# Prototype_V0_2.net
KiCad netlist of a schematic drawn in EAGLE
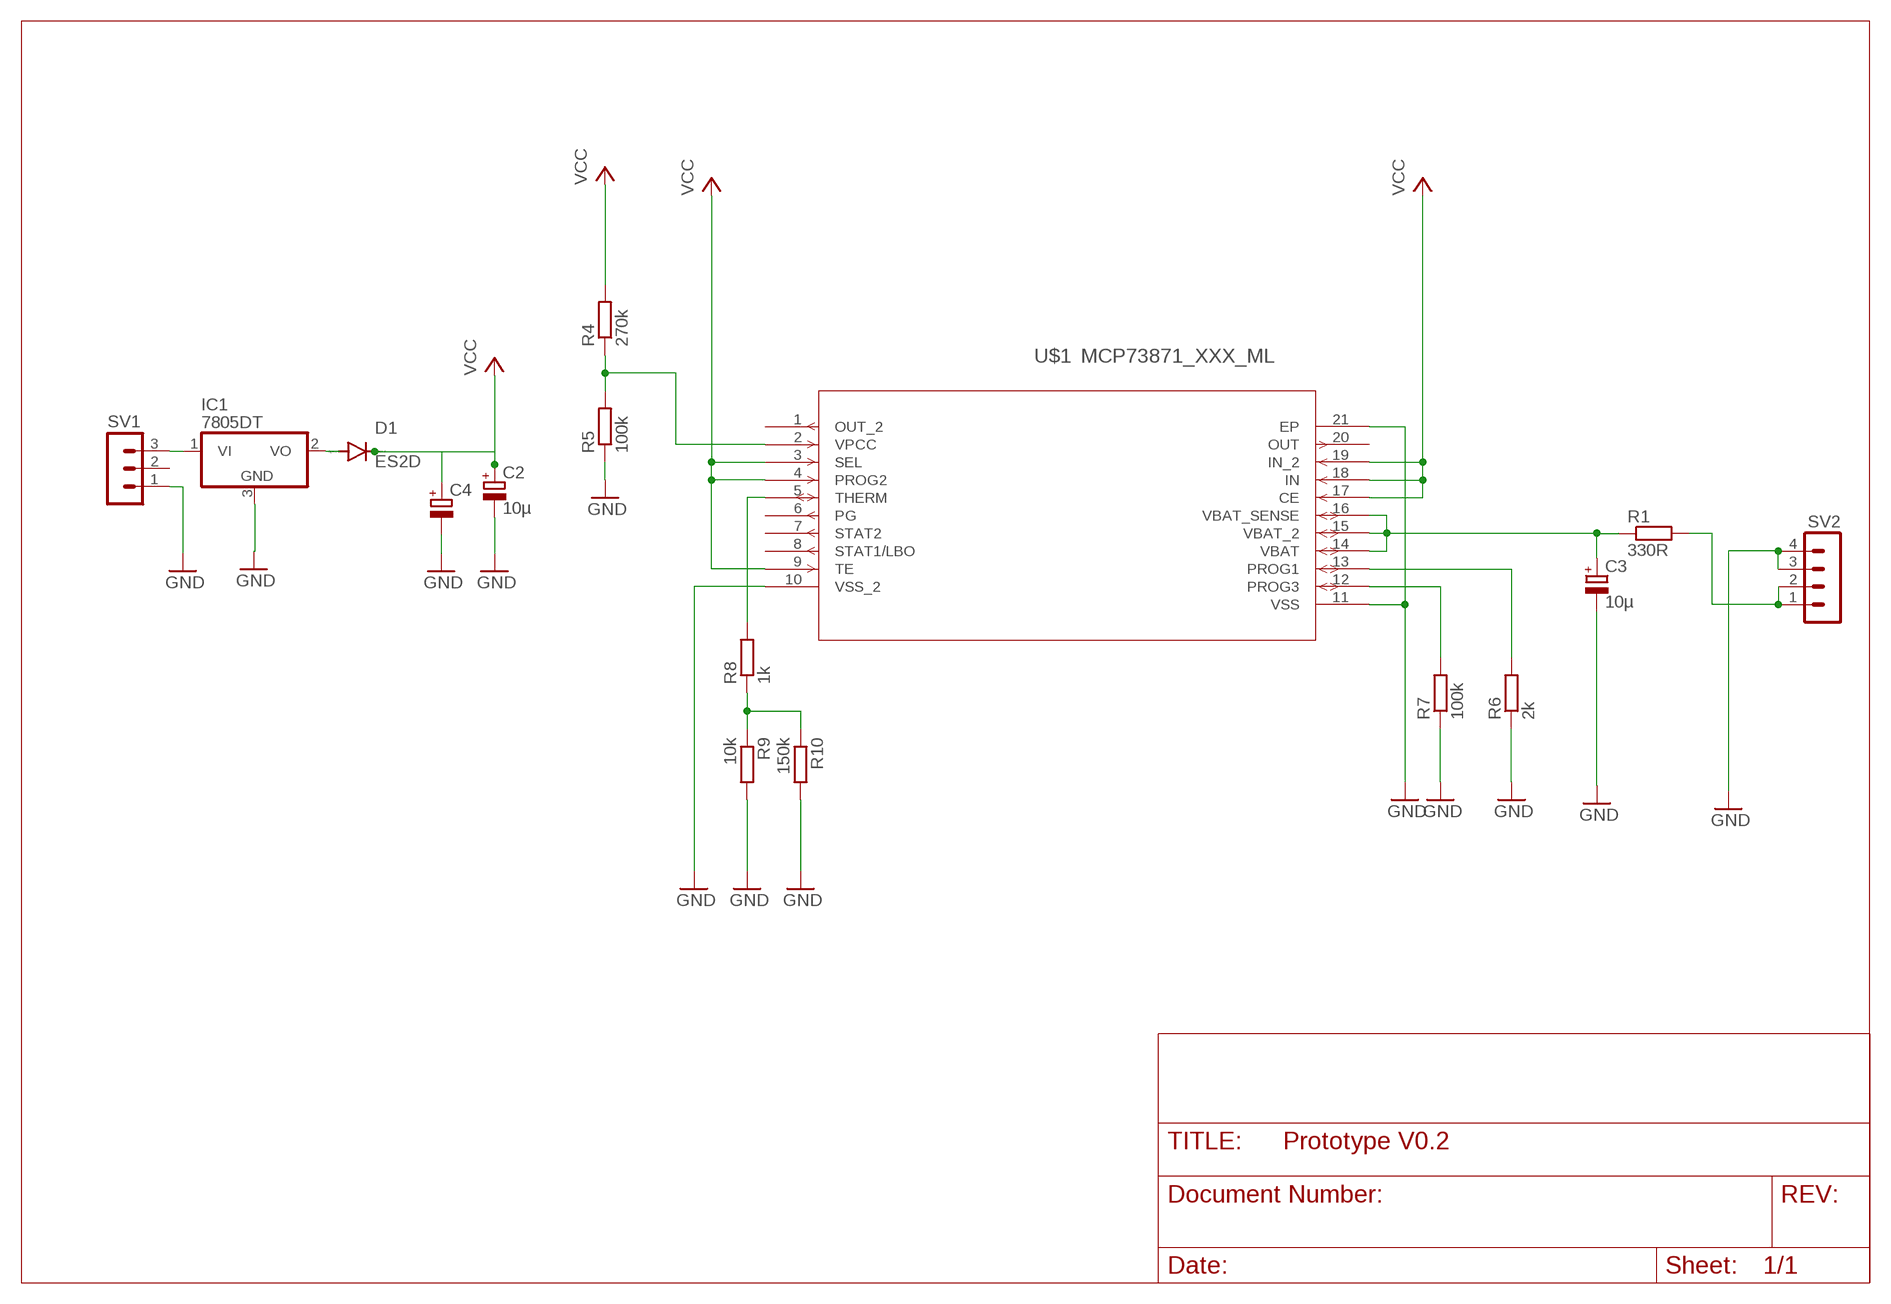
[diagram p0: schematic, sheet 1]

(export (version "E")
  (design (tool "Eeschema 10.0.6"))
  (components
    (comp (ref "C2")
      (value "10µ")
      (footprint "eagle-import:153CLV-0505")
      (libsource (lib "eagle-import") (part "CPOL-EU153CLV-0505"))
    )
    (comp (ref "C3")
      (value "10µ")
      (footprint "eagle-import:153CLV-0505")
      (libsource (lib "eagle-import") (part "CPOL-EU153CLV-0505"))
    )
    (comp (ref "C4")
      (value "CPOL-EUE2.5-6")
      (footprint "eagle-import:E2,5-6")
      (libsource (lib "eagle-import") (part "CPOL-EUE2.5-6"))
    )
    (comp (ref "D1")
      (value "ES2D")
      (footprint "eagle-import:SMB")
      (libsource (lib "eagle-import") (part "ES2D"))
    )
    (comp (ref "IC1")
      (value "7805DT")
      (footprint "eagle-import:TO252")
      (libsource (lib "eagle-import") (part "78DT05"))
    )
    (comp (ref "R1")
      (value "330R")
      (footprint "eagle-import:R0603")
      (libsource (lib "eagle-import") (part "R-EU_R0603"))
    )
    (comp (ref "R4")
      (value "270k")
      (footprint "eagle-import:R0603")
      (libsource (lib "eagle-import") (part "R-EU_R0603"))
    )
    (comp (ref "R5")
      (value "100k")
      (footprint "eagle-import:R0603")
      (libsource (lib "eagle-import") (part "R-EU_R0603"))
    )
    (comp (ref "R6")
      (value "2k")
      (footprint "eagle-import:R0603")
      (libsource (lib "eagle-import") (part "R-EU_R0603"))
    )
    (comp (ref "R7")
      (value "100k")
      (footprint "eagle-import:R0603")
      (libsource (lib "eagle-import") (part "R-EU_R0603"))
    )
    (comp (ref "R8")
      (value "1k")
      (footprint "eagle-import:R0603")
      (libsource (lib "eagle-import") (part "R-EU_R0603"))
    )
    (comp (ref "R9")
      (value "10k")
      (footprint "eagle-import:R0603")
      (libsource (lib "eagle-import") (part "R-EU_R0603"))
    )
    (comp (ref "R10")
      (value "150k")
      (footprint "eagle-import:R0603")
      (libsource (lib "eagle-import") (part "R-EU_R0603"))
    )
    (comp (ref "SV1")
      (value "MA03-1")
      (footprint "eagle-import:MA03-1")
      (libsource (lib "eagle-import") (part "MA03-1"))
    )
    (comp (ref "SV2")
      (value "MA04-1")
      (footprint "eagle-import:MA04-1")
      (libsource (lib "eagle-import") (part "MA04-1"))
    )
    (comp (ref "U$1")
      (value "MCP73871_XXX_ML")
      (footprint "eagle-import:QFN20_4X4MC")
      (libsource (lib "eagle-import") (part "MCP73871_XXX_ML"))
    )
  )
  (nets
    (net (code "1") (name "GND") (class "Default")
      (node (ref "C2") (pin "-") (pinfunction "-_-") (pintype "passive"))
      (node (ref "C3") (pin "-") (pinfunction "-_-") (pintype "passive"))
      (node (ref "C4") (pin "-") (pinfunction "-_-") (pintype "passive"))
      (node (ref "IC1") (pin "3") (pinfunction "GND_3") (pintype "passive"))
      (node (ref "R10") (pin "2") (pinfunction "2_2") (pintype "passive"))
      (node (ref "R5") (pin "1") (pinfunction "1_1") (pintype "passive"))
      (node (ref "R6") (pin "1") (pinfunction "1_1") (pintype "passive"))
      (node (ref "R7") (pin "1") (pinfunction "1_1") (pintype "passive"))
      (node (ref "R9") (pin "2") (pinfunction "2_2") (pintype "passive"))
      (node (ref "SV1") (pin "1") (pinfunction "1_1") (pintype "passive"))
      (node (ref "SV2") (pin "3") (pinfunction "3_3") (pintype "passive"))
      (node (ref "SV2") (pin "4") (pinfunction "4_4") (pintype "passive"))
      (node (ref "U$1") (pin "10") (pinfunction "VSS_2_10") (pintype "power_in"))
      (node (ref "U$1") (pin "11") (pinfunction "VSS_11") (pintype "power_in"))
      (node (ref "U$1") (pin "21") (pinfunction "EP_21") (pintype "passive"))
    )
    (net (code "2") (name "Net-(IC1-VI)") (class "Default")
      (node (ref "IC1") (pin "1") (pinfunction "VI_1") (pintype "input"))
      (node (ref "SV1") (pin "3") (pinfunction "3_3") (pintype "passive"))
    )
    (net (code "3") (name "Net-(IC1-VO)") (class "Default")
      (node (ref "D1") (pin "A") (pinfunction "A_A") (pintype "passive"))
      (node (ref "IC1") (pin "2") (pinfunction "VO_2") (pintype "passive"))
    )
    (net (code "4") (name "Net-(R1-Pad2)") (class "Default")
      (node (ref "R1") (pin "2") (pinfunction "2_2") (pintype "passive"))
      (node (ref "SV2") (pin "1") (pinfunction "1_1") (pintype "passive"))
      (node (ref "SV2") (pin "2") (pinfunction "2_2") (pintype "passive"))
    )
    (net (code "5") (name "Net-(R10-Pad1)") (class "Default")
      (node (ref "R10") (pin "1") (pinfunction "1_1") (pintype "passive"))
      (node (ref "R8") (pin "1") (pinfunction "1_1") (pintype "passive"))
      (node (ref "R9") (pin "1") (pinfunction "1_1") (pintype "passive"))
    )
    (net (code "6") (name "Net-(U$1-PROG1)") (class "Default")
      (node (ref "R6") (pin "2") (pinfunction "2_2") (pintype "passive"))
      (node (ref "U$1") (pin "13") (pinfunction "PROG1_13") (pintype "bidirectional"))
    )
    (net (code "7") (name "Net-(U$1-PROG3)") (class "Default")
      (node (ref "R7") (pin "2") (pinfunction "2_2") (pintype "passive"))
      (node (ref "U$1") (pin "12") (pinfunction "PROG3_12") (pintype "bidirectional"))
    )
    (net (code "8") (name "Net-(U$1-THERM)") (class "Default")
      (node (ref "R8") (pin "2") (pinfunction "2_2") (pintype "passive"))
      (node (ref "U$1") (pin "5") (pinfunction "THERM_5") (pintype "bidirectional"))
    )
    (net (code "9") (name "Net-(U$1-VBAT)") (class "Default")
      (node (ref "C3") (pin "+") (pinfunction "+_+") (pintype "passive"))
      (node (ref "U$1") (pin "14") (pinfunction "VBAT_14") (pintype "bidirectional"))
      (node (ref "U$1") (pin "15") (pinfunction "VBAT_2_15") (pintype "bidirectional"))
      (node (ref "U$1") (pin "16") (pinfunction "VBAT_SENSE_16") (pintype "bidirectional"))
    )
    (net (code "10") (name "Net-(U$1-VPCC)") (class "Default")
      (node (ref "R4") (pin "1") (pinfunction "1_1") (pintype "passive"))
      (node (ref "R5") (pin "2") (pinfunction "2_2") (pintype "passive"))
      (node (ref "U$1") (pin "2") (pinfunction "VPCC_2") (pintype "input"))
    )
    (net (code "11") (name "VCC") (class "Default")
      (node (ref "C2") (pin "+") (pinfunction "+_+") (pintype "passive"))
      (node (ref "C4") (pin "+") (pinfunction "+_+") (pintype "passive"))
      (node (ref "D1") (pin "C") (pinfunction "C_C") (pintype "passive"))
      (node (ref "R4") (pin "2") (pinfunction "2_2") (pintype "passive"))
      (node (ref "U$1") (pin "17") (pinfunction "CE_17") (pintype "input"))
      (node (ref "U$1") (pin "18") (pinfunction "IN_18") (pintype "input"))
      (node (ref "U$1") (pin "19") (pinfunction "IN_2_19") (pintype "input"))
      (node (ref "U$1") (pin "3") (pinfunction "SEL_3") (pintype "input"))
      (node (ref "U$1") (pin "4") (pinfunction "PROG2_4") (pintype "input"))
      (node (ref "U$1") (pin "9") (pinfunction "TE_9") (pintype "input"))
    )
    (net (code "12") (name "unconnected-(R1-Pad1)") (class "Default")
      (node (ref "R1") (pin "1") (pinfunction "1_1") (pintype "passive"))
    )
    (net (code "13") (name "unconnected-(SV1-Pad2)") (class "Default")
      (node (ref "SV1") (pin "2") (pinfunction "2_2") (pintype "passive"))
    )
    (net (code "14") (name "unconnected-(U$1-OUT-Pad20)") (class "Default")
      (node (ref "U$1") (pin "20") (pinfunction "OUT_20") (pintype "output"))
    )
    (net (code "15") (name "unconnected-(U$1-OUT_2-Pad1)") (class "Default")
      (node (ref "U$1") (pin "1") (pinfunction "OUT_2_1") (pintype "output"))
    )
    (net (code "16") (name "unconnected-(U$1-PG-Pad6)") (class "Default")
      (node (ref "U$1") (pin "6") (pinfunction "PG_6") (pintype "output"))
    )
    (net (code "17") (name "unconnected-(U$1-STAT1{slash}LBO-Pad8)") (class "Default")
      (node (ref "U$1") (pin "8") (pinfunction "STAT1/LBO_8") (pintype "output"))
    )
    (net (code "18") (name "unconnected-(U$1-STAT2-Pad7)") (class "Default")
      (node (ref "U$1") (pin "7") (pinfunction "STAT2_7") (pintype "output"))
    )
  )
)
